# TPIC6C.net
KiCad netlist of a schematic drawn in EAGLE
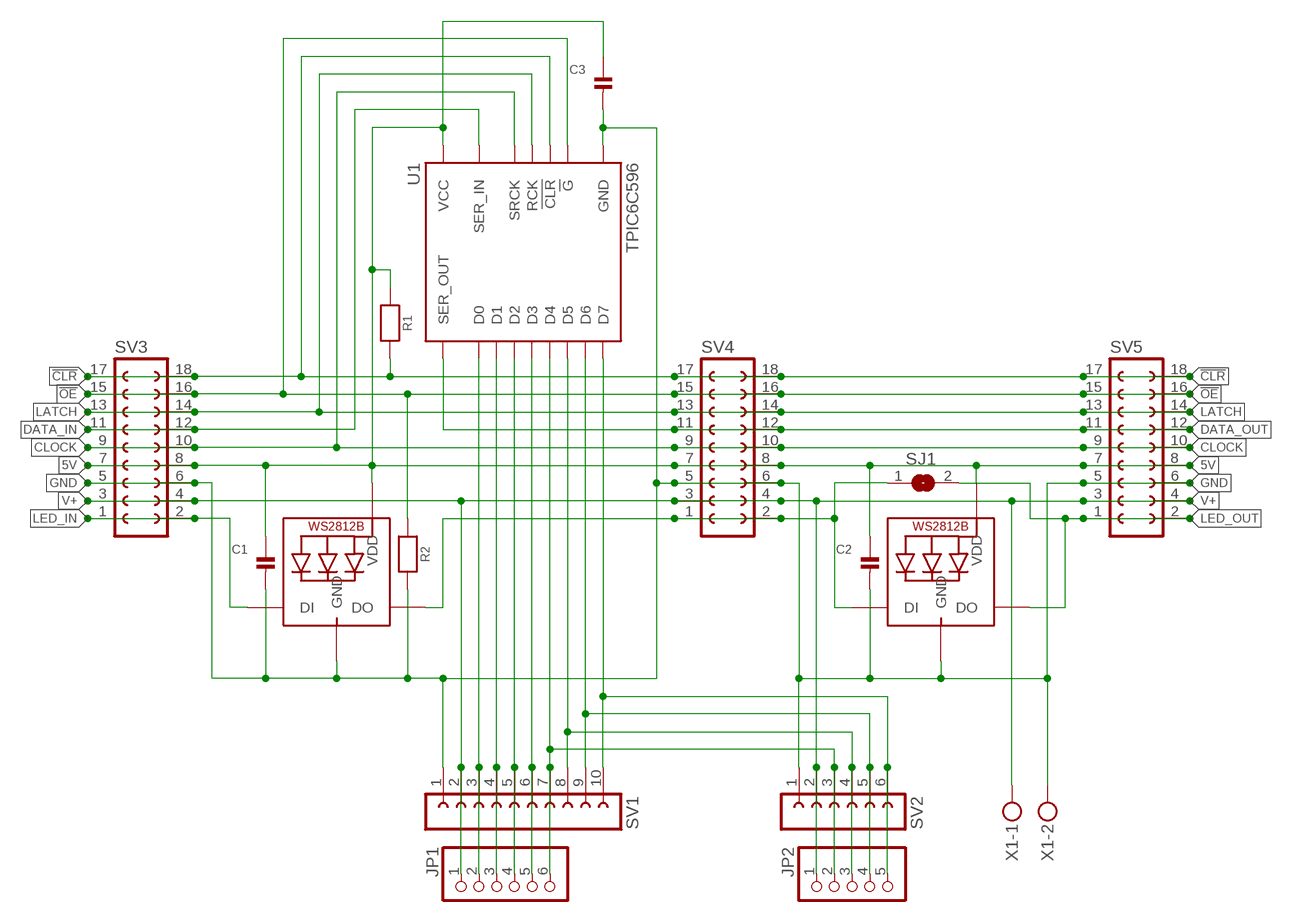
[diagram p0: schematic, sheet 1]

(export (version "E")
  (design (tool "Eeschema 10.0.6"))
  (components
    (comp (ref "C1")
      (value "CAP_CERAMIC0603")
      (footprint "eagle-import:0603")
      (libsource (lib "eagle-import") (part "CAP_CERAMIC0603"))
    )
    (comp (ref "C2")
      (value "CAP_CERAMIC0603")
      (footprint "eagle-import:0603")
      (libsource (lib "eagle-import") (part "CAP_CERAMIC0603"))
    )
    (comp (ref "C3")
      (value "CAP_CERAMIC0603")
      (footprint "eagle-import:0603")
      (libsource (lib "eagle-import") (part "CAP_CERAMIC0603"))
    )
    (comp (ref "JP1")
      (value "HEADER-1X61X06_1.27MM")
      (footprint "eagle-import:1X06_1.27MM")
      (libsource (lib "eagle-import") (part "HEADER-1X61X06_1.27MM"))
    )
    (comp (ref "JP2")
      (value "HEADER-1X51.27MM")
      (footprint "eagle-import:1X05_1.27MM")
      (libsource (lib "eagle-import") (part "HEADER-1X51.27MM"))
    )
    (comp (ref "LED1")
      (value "WS2812B5050")
      (footprint "eagle-import:WS2812B")
      (libsource (lib "eagle-import") (part "WS2812B5050"))
    )
    (comp (ref "LED2")
      (value "WS2812B5050")
      (footprint "eagle-import:WS2812B")
      (libsource (lib "eagle-import") (part "WS2812B5050"))
    )
    (comp (ref "R1")
      (value "MICROBUILDER_RESISTOR_0603_NOOUT")
      (footprint "eagle-import:MICROBUILDER_0603-NO")
      (libsource (lib "eagle-import") (part "MICROBUILDER_RESISTOR_0603_NOOUT"))
    )
    (comp (ref "R2")
      (value "MICROBUILDER_RESISTOR_0603_NOOUT")
      (footprint "eagle-import:MICROBUILDER_0603-NO")
      (libsource (lib "eagle-import") (part "MICROBUILDER_RESISTOR_0603_NOOUT"))
    )
    (comp (ref "SJ1")
      (value "SOLDERJUMPER")
      (footprint "eagle-import:SOLDERJUMPER_ARROW_NOPASTE")
      (libsource (lib "eagle-import") (part "SOLDERJUMPER"))
    )
    (comp (ref "SV1")
      (value "FE10-1")
      (footprint "eagle-import:FE10")
      (libsource (lib "eagle-import") (part "FE10-1"))
    )
    (comp (ref "SV2")
      (value "FE06-1")
      (footprint "eagle-import:FE06")
      (libsource (lib "eagle-import") (part "FE06-1"))
    )
    (comp (ref "SV3")
      (value "FE09-2NOSILK")
      (footprint "eagle-import:FE09-2_NOSILK")
      (libsource (lib "eagle-import") (part "FE09-2NOSILK"))
    )
    (comp (ref "SV4")
      (value "FE09-2NOSILK")
      (footprint "eagle-import:FE09-2_NOSILK")
      (libsource (lib "eagle-import") (part "FE09-2NOSILK"))
    )
    (comp (ref "SV5")
      (value "FE09-2NOSILK")
      (footprint "eagle-import:FE09-2_NOSILK")
      (libsource (lib "eagle-import") (part "FE09-2NOSILK"))
    )
    (comp (ref "U1")
      (value "TPIC6C596")
      (footprint "eagle-import:SO16")
      (libsource (lib "eagle-import") (part "TPIC6C596SOIC"))
    )
    (comp (ref "X1")
      (value "MKDSN1,5/2-5,08")
      (footprint "eagle-import:MKDSN1,5_2-5,08")
      (libsource (lib "eagle-import") (part "MKDSN1,5/2-5,08"))
    )
  )
  (nets
    (net (code "1") (name "/~{CLR}") (class "Default")
      (node (ref "R1") (pin "2") (pinfunction "2_2") (pintype "passive"))
      (node (ref "SV3") (pin "17") (pinfunction "17_17") (pintype "passive"))
      (node (ref "SV3") (pin "18") (pinfunction "18_18") (pintype "passive"))
      (node (ref "SV4") (pin "17") (pinfunction "17_17") (pintype "passive"))
      (node (ref "SV4") (pin "18") (pinfunction "18_18") (pintype "passive"))
      (node (ref "SV5") (pin "17") (pinfunction "17_17") (pintype "passive"))
      (node (ref "SV5") (pin "18") (pinfunction "18_18") (pintype "passive"))
      (node (ref "U1") (pin "7") (pinfunction "~{CLR}_7") (pintype "input"))
    )
    (net (code "2") (name "/~{OE}") (class "Default")
      (node (ref "R2") (pin "1") (pinfunction "1_1") (pintype "passive"))
      (node (ref "SV3") (pin "15") (pinfunction "15_15") (pintype "passive"))
      (node (ref "SV3") (pin "16") (pinfunction "16_16") (pintype "passive"))
      (node (ref "SV4") (pin "15") (pinfunction "15_15") (pintype "passive"))
      (node (ref "SV4") (pin "16") (pinfunction "16_16") (pintype "passive"))
      (node (ref "SV5") (pin "15") (pinfunction "15_15") (pintype "passive"))
      (node (ref "SV5") (pin "16") (pinfunction "16_16") (pintype "passive"))
      (node (ref "U1") (pin "8") (pinfunction "~{G}_8") (pintype "input"))
    )
    (net (code "3") (name "5V") (class "Default")
      (node (ref "C1") (pin "1") (pinfunction "P$1_1") (pintype "passive"))
      (node (ref "C2") (pin "1") (pinfunction "P$1_1") (pintype "passive"))
      (node (ref "C3") (pin "1") (pinfunction "P$1_1") (pintype "passive"))
      (node (ref "LED1") (pin "1-VDD") (pinfunction "VDD_1-VDD") (pintype "power_in"))
      (node (ref "LED2") (pin "1-VDD") (pinfunction "VDD_1-VDD") (pintype "power_in"))
      (node (ref "R1") (pin "1") (pinfunction "1_1") (pintype "passive"))
      (node (ref "SV3") (pin "7") (pinfunction "7_7") (pintype "passive"))
      (node (ref "SV3") (pin "8") (pinfunction "8_8") (pintype "passive"))
      (node (ref "SV4") (pin "7") (pinfunction "7_7") (pintype "passive"))
      (node (ref "SV4") (pin "8") (pinfunction "8_8") (pintype "passive"))
      (node (ref "SV5") (pin "7") (pinfunction "7_7") (pintype "passive"))
      (node (ref "SV5") (pin "8") (pinfunction "8_8") (pintype "passive"))
      (node (ref "U1") (pin "1") (pinfunction "VCC_1") (pintype "power_in"))
    )
    (net (code "4") (name "CLOCK") (class "Default")
      (node (ref "SV3") (pin "10") (pinfunction "10_10") (pintype "passive"))
      (node (ref "SV3") (pin "9") (pinfunction "9_9") (pintype "passive"))
      (node (ref "SV4") (pin "10") (pinfunction "10_10") (pintype "passive"))
      (node (ref "SV4") (pin "9") (pinfunction "9_9") (pintype "passive"))
      (node (ref "SV5") (pin "10") (pinfunction "10_10") (pintype "passive"))
      (node (ref "SV5") (pin "9") (pinfunction "9_9") (pintype "passive"))
      (node (ref "U1") (pin "15") (pinfunction "SRCK_15") (pintype "input"))
    )
    (net (code "5") (name "DATA_IN") (class "Default")
      (node (ref "SV3") (pin "11") (pinfunction "11_11") (pintype "passive"))
      (node (ref "SV3") (pin "12") (pinfunction "12_12") (pintype "passive"))
      (node (ref "U1") (pin "2") (pinfunction "SER_IN_2") (pintype "input"))
    )
    (net (code "6") (name "DATA_OUT") (class "Default")
      (node (ref "SV4") (pin "11") (pinfunction "11_11") (pintype "passive"))
      (node (ref "SV4") (pin "12") (pinfunction "12_12") (pintype "passive"))
      (node (ref "SV5") (pin "11") (pinfunction "11_11") (pintype "passive"))
      (node (ref "SV5") (pin "12") (pinfunction "12_12") (pintype "passive"))
      (node (ref "U1") (pin "9") (pinfunction "SER_OUT_9") (pintype "output"))
    )
    (net (code "7") (name "GND") (class "Default")
      (node (ref "C1") (pin "2") (pinfunction "P$2_2") (pintype "passive"))
      (node (ref "C2") (pin "2") (pinfunction "P$2_2") (pintype "passive"))
      (node (ref "C3") (pin "2") (pinfunction "P$2_2") (pintype "passive"))
      (node (ref "LED1") (pin "3-GND") (pinfunction "GND_3-GND") (pintype "power_in"))
      (node (ref "LED2") (pin "3-GND") (pinfunction "GND_3-GND") (pintype "power_in"))
      (node (ref "R2") (pin "2") (pinfunction "2_2") (pintype "passive"))
      (node (ref "SV1") (pin "1") (pinfunction "1_1") (pintype "passive"))
      (node (ref "SV2") (pin "1") (pinfunction "1_1") (pintype "passive"))
      (node (ref "SV3") (pin "5") (pinfunction "5_5") (pintype "passive"))
      (node (ref "SV3") (pin "6") (pinfunction "6_6") (pintype "passive"))
      (node (ref "SV4") (pin "5") (pinfunction "5_5") (pintype "passive"))
      (node (ref "SV4") (pin "6") (pinfunction "6_6") (pintype "passive"))
      (node (ref "SV5") (pin "5") (pinfunction "5_5") (pintype "passive"))
      (node (ref "SV5") (pin "6") (pinfunction "6_6") (pintype "passive"))
      (node (ref "U1") (pin "16") (pinfunction "GND_16") (pintype "power_in"))
      (node (ref "X1") (pin "2") (pinfunction "KL_2") (pintype "passive"))
    )
    (net (code "8") (name "LATCH") (class "Default")
      (node (ref "SV3") (pin "13") (pinfunction "13_13") (pintype "passive"))
      (node (ref "SV3") (pin "14") (pinfunction "14_14") (pintype "passive"))
      (node (ref "SV4") (pin "13") (pinfunction "13_13") (pintype "passive"))
      (node (ref "SV4") (pin "14") (pinfunction "14_14") (pintype "passive"))
      (node (ref "SV5") (pin "13") (pinfunction "13_13") (pintype "passive"))
      (node (ref "SV5") (pin "14") (pinfunction "14_14") (pintype "passive"))
      (node (ref "U1") (pin "10") (pinfunction "RCK_10") (pintype "input"))
    )
    (net (code "9") (name "LED_IN") (class "Default")
      (node (ref "LED1") (pin "4-DIN") (pinfunction "DI_4-DIN") (pintype "input"))
      (node (ref "SV3") (pin "1") (pinfunction "1_1") (pintype "passive"))
      (node (ref "SV3") (pin "2") (pinfunction "2_2") (pintype "passive"))
    )
    (net (code "10") (name "LED_OUT") (class "Default")
      (node (ref "LED2") (pin "2-DOUT") (pinfunction "DO_2-DOUT") (pintype "output"))
      (node (ref "SJ1") (pin "2") (pinfunction "2_2") (pintype "passive"))
      (node (ref "SV5") (pin "1") (pinfunction "1_1") (pintype "passive"))
      (node (ref "SV5") (pin "2") (pinfunction "2_2") (pintype "passive"))
    )
    (net (code "11") (name "Net-(LED1-DO)") (class "Default")
      (node (ref "LED1") (pin "2-DOUT") (pinfunction "DO_2-DOUT") (pintype "output"))
      (node (ref "LED2") (pin "4-DIN") (pinfunction "DI_4-DIN") (pintype "input"))
      (node (ref "SJ1") (pin "1") (pinfunction "1_1") (pintype "passive"))
      (node (ref "SV4") (pin "1") (pinfunction "1_1") (pintype "passive"))
      (node (ref "SV4") (pin "2") (pinfunction "2_2") (pintype "passive"))
    )
    (net (code "12") (name "Net-(U1-D0)") (class "Default")
      (node (ref "JP1") (pin "2") (pinfunction "2_2") (pintype "passive"))
      (node (ref "SV1") (pin "3") (pinfunction "3_3") (pintype "passive"))
      (node (ref "U1") (pin "3") (pinfunction "D0_3") (pintype "output"))
    )
    (net (code "13") (name "Net-(U1-D1)") (class "Default")
      (node (ref "JP1") (pin "3") (pinfunction "3_3") (pintype "passive"))
      (node (ref "SV1") (pin "4") (pinfunction "4_4") (pintype "passive"))
      (node (ref "U1") (pin "4") (pinfunction "D1_4") (pintype "output"))
    )
    (net (code "14") (name "Net-(U1-D2)") (class "Default")
      (node (ref "JP1") (pin "4") (pinfunction "4_4") (pintype "passive"))
      (node (ref "SV1") (pin "5") (pinfunction "5_5") (pintype "passive"))
      (node (ref "U1") (pin "5") (pinfunction "D2_5") (pintype "output"))
    )
    (net (code "15") (name "Net-(U1-D3)") (class "Default")
      (node (ref "JP1") (pin "5") (pinfunction "5_5") (pintype "passive"))
      (node (ref "SV1") (pin "6") (pinfunction "6_6") (pintype "passive"))
      (node (ref "U1") (pin "6") (pinfunction "D3_6") (pintype "output"))
    )
    (net (code "16") (name "Net-(U1-D4)") (class "Default")
      (node (ref "JP1") (pin "6") (pinfunction "6_6") (pintype "passive"))
      (node (ref "JP2") (pin "2") (pinfunction "2_2") (pintype "passive"))
      (node (ref "SV1") (pin "7") (pinfunction "7_7") (pintype "passive"))
      (node (ref "SV2") (pin "3") (pinfunction "3_3") (pintype "passive"))
      (node (ref "U1") (pin "11") (pinfunction "D4_11") (pintype "output"))
    )
    (net (code "17") (name "Net-(U1-D5)") (class "Default")
      (node (ref "JP2") (pin "3") (pinfunction "3_3") (pintype "passive"))
      (node (ref "SV1") (pin "8") (pinfunction "8_8") (pintype "passive"))
      (node (ref "SV2") (pin "4") (pinfunction "4_4") (pintype "passive"))
      (node (ref "U1") (pin "12") (pinfunction "D5_12") (pintype "output"))
    )
    (net (code "18") (name "Net-(U1-D6)") (class "Default")
      (node (ref "JP2") (pin "4") (pinfunction "4_4") (pintype "passive"))
      (node (ref "SV1") (pin "9") (pinfunction "9_9") (pintype "passive"))
      (node (ref "SV2") (pin "5") (pinfunction "5_5") (pintype "passive"))
      (node (ref "U1") (pin "13") (pinfunction "D6_13") (pintype "output"))
    )
    (net (code "19") (name "Net-(U1-D7)") (class "Default")
      (node (ref "JP2") (pin "5") (pinfunction "5_5") (pintype "passive"))
      (node (ref "SV1") (pin "10") (pinfunction "10_10") (pintype "passive"))
      (node (ref "SV2") (pin "6") (pinfunction "6_6") (pintype "passive"))
      (node (ref "U1") (pin "14") (pinfunction "D7_14") (pintype "output"))
    )
    (net (code "20") (name "V+") (class "Default")
      (node (ref "JP1") (pin "1") (pinfunction "1_1") (pintype "passive"))
      (node (ref "JP2") (pin "1") (pinfunction "1_1") (pintype "passive"))
      (node (ref "SV1") (pin "2") (pinfunction "2_2") (pintype "passive"))
      (node (ref "SV2") (pin "2") (pinfunction "2_2") (pintype "passive"))
      (node (ref "SV3") (pin "3") (pinfunction "3_3") (pintype "passive"))
      (node (ref "SV3") (pin "4") (pinfunction "4_4") (pintype "passive"))
      (node (ref "SV4") (pin "3") (pinfunction "3_3") (pintype "passive"))
      (node (ref "SV4") (pin "4") (pinfunction "4_4") (pintype "passive"))
      (node (ref "SV5") (pin "3") (pinfunction "3_3") (pintype "passive"))
      (node (ref "SV5") (pin "4") (pinfunction "4_4") (pintype "passive"))
      (node (ref "X1") (pin "1") (pinfunction "KL_1") (pintype "passive"))
    )
  )
)
